# ZAtechSensor3_v1_01.net
KiCad netlist of a schematic drawn in Altium Designer
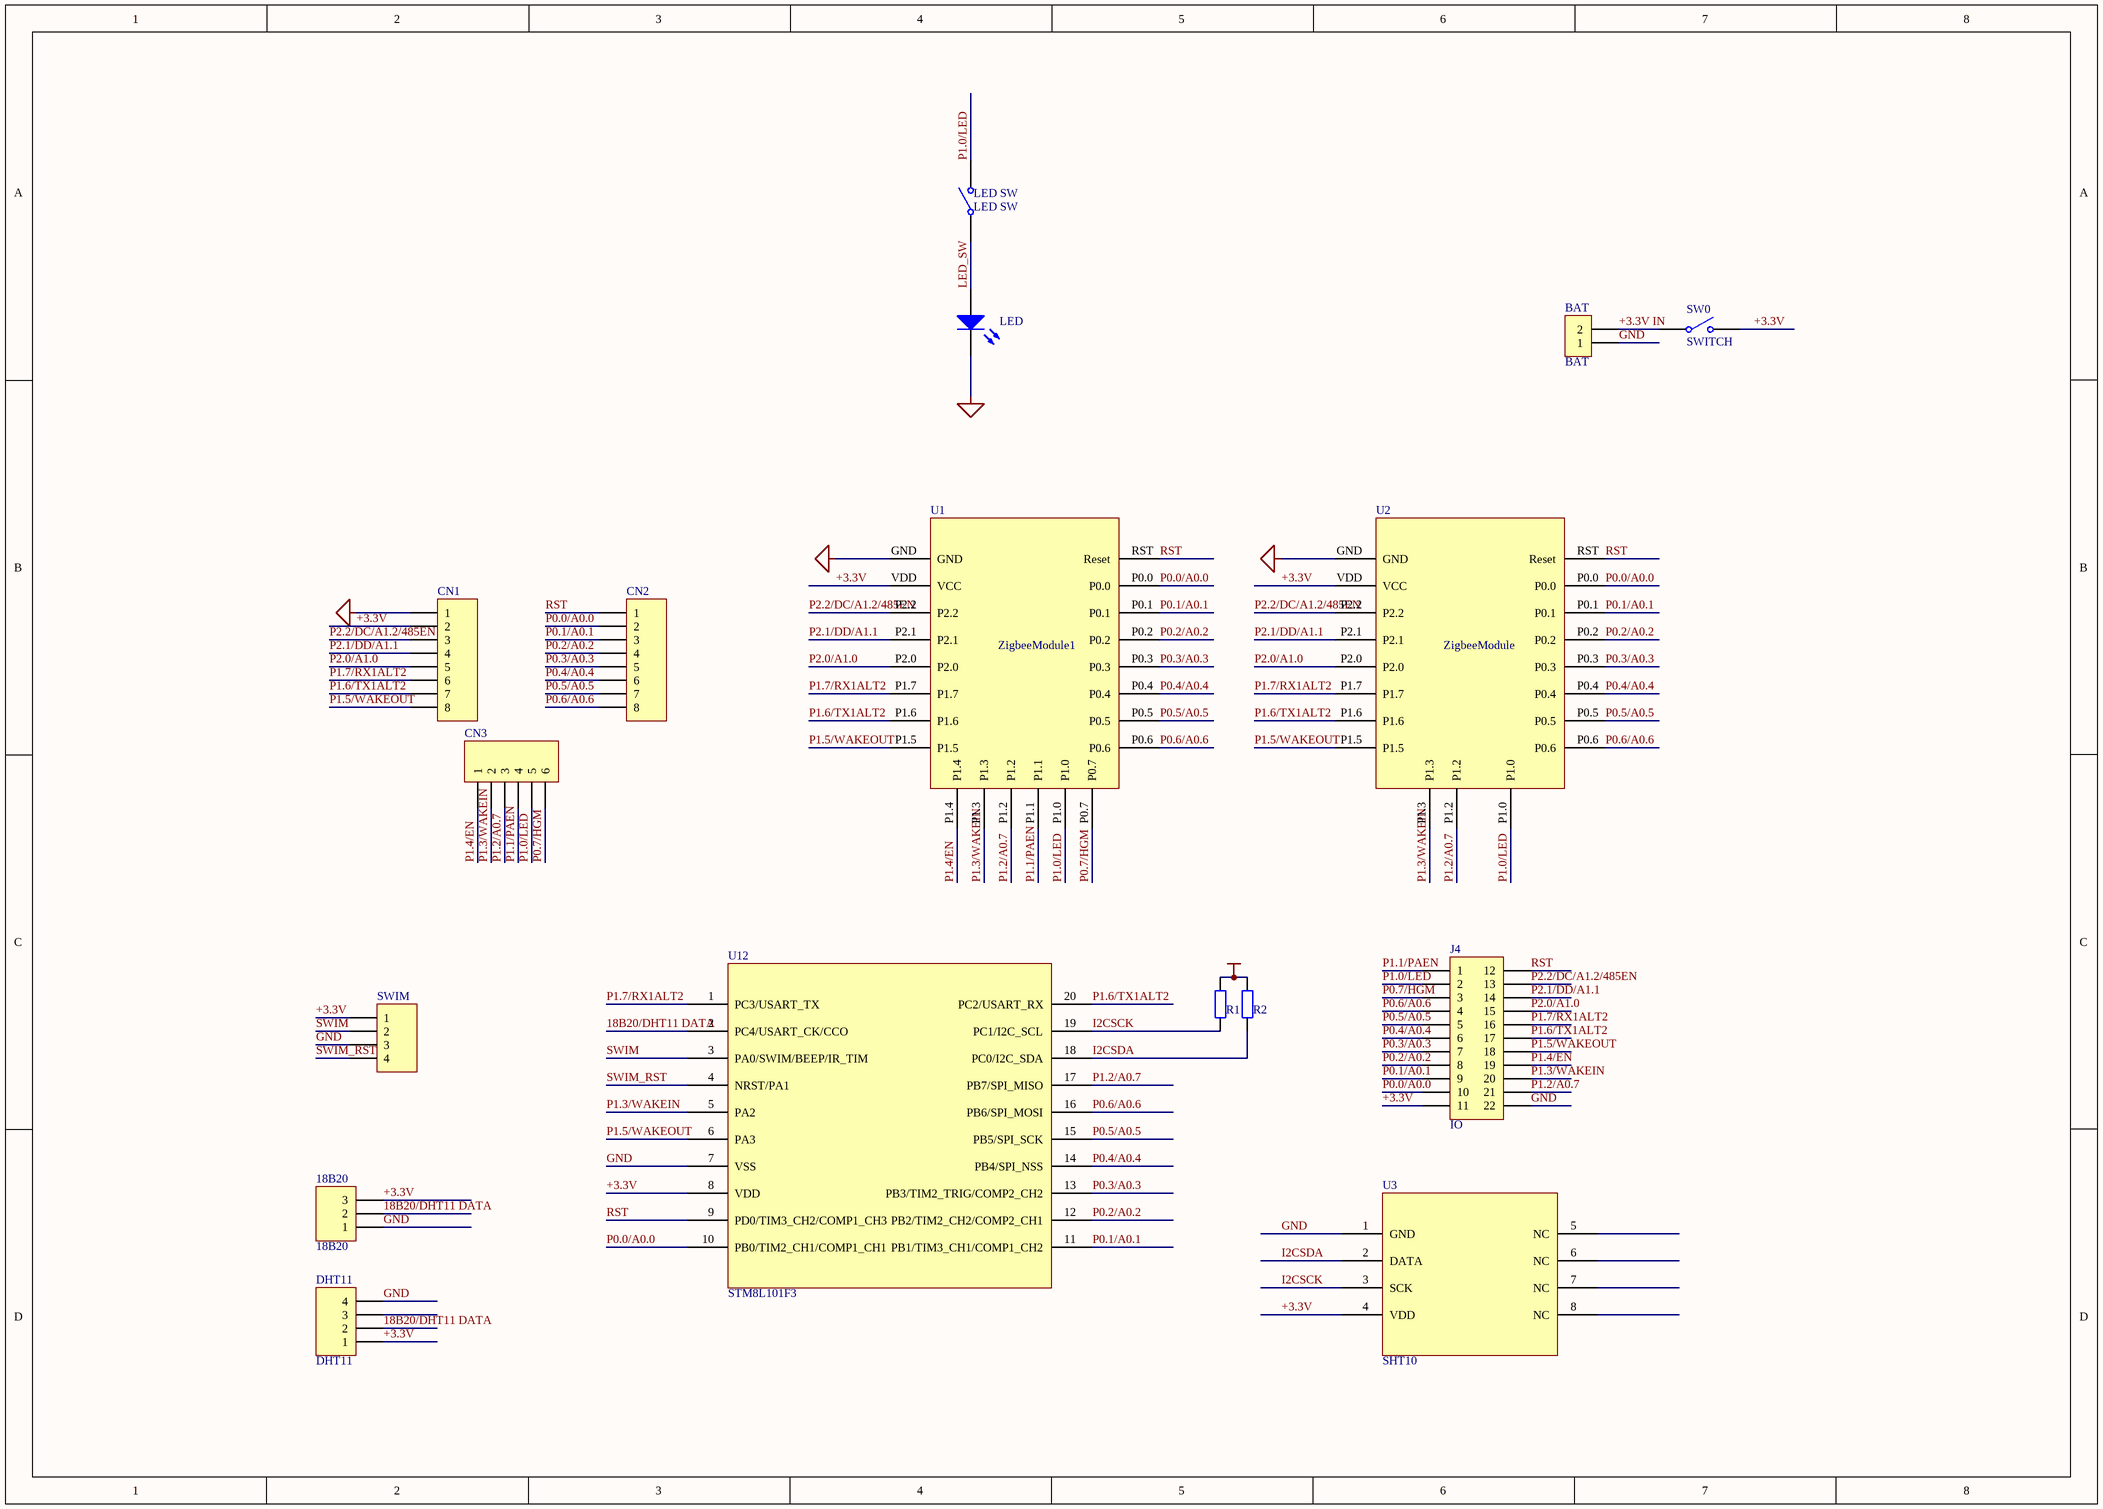
[diagram p0: ZAtechSensor3 v1_01.SCHDOC]

(export (version "E")
  (design (tool "Eeschema 10.0.6"))
  (components
    (comp (ref "18B20")
      (value "18B20")
      (footprint "BCY-W3")
      (description "Header, 3-Pin")
      (fields (field (name "PUBLISHER") "Altium Limited"))
      (libsource (lib "Miscellaneous Connectors") (part "Header 3"))
    )
    (comp (ref "BAT") (value "BAT") (footprint "HDR1X2") (libsource (lib "总lib库") (part "CON2")))
    (comp (ref "CN1")
      (value "~")
      (footprint "HDR1X8")
      (description "Header, 8-Pin")
      (fields (field (name "PUBLISHER") "Altium Limited"))
      (libsource (lib "Miscellaneous Connectors") (part "Header 8"))
    )
    (comp (ref "CN2")
      (value "~")
      (footprint "HDR1X8")
      (description "Header, 8-Pin")
      (fields (field (name "PUBLISHER") "Altium Limited"))
      (libsource (lib "Miscellaneous Connectors") (part "Header 8"))
    )
    (comp (ref "CN3")
      (value "~")
      (footprint "HDR1X6")
      (description "Header, 6-Pin")
      (fields (field (name "PUBLISHER") "Altium Limited"))
      (libsource (lib "Miscellaneous Connectors") (part "Header 6"))
    )
    (comp (ref "DHT11")
      (value "DHT11")
      (footprint "HDR1X4")
      (description "Header, 4-Pin")
      (fields (field (name "PUBLISHER") "Altium Limited"))
      (libsource (lib "") (part "Header 4_1"))
    )
    (comp (ref "J4")
      (value "IO")
      (footprint "HDR2X11_CEN")
      (description "Header, 11-Pin, Dual row")
      (fields (field (name "PUBLISHER") "Altium Limited"))
      (libsource (lib "Miscellaneous Connectors") (part "Header 11X2A"))
    )
    (comp (ref "LED")
      (value "LED3")
      (footprint "LED1-3MM")
      (description "Typical BLUE SiC LED")
      (fields (field (name "PUBLISHER") "Altium Limited"))
      (libsource (lib "Miscellaneous Devices") (part "LED3"))
    )
    (comp (ref "LED SW")
      (value "LED SW")
      (footprint "HDR1X2")
      (description "Single-Pole, Single-Throw Switch")
      (fields (field (name "PUBLISHER") "Altium Limited"))
      (libsource (lib "Miscellaneous Devices") (part "SW-SPST"))
    )
    (comp (ref "R1")
      (value "4.7K")
      (footprint "0402")
      (description "Resistor")
      (libsource (lib "Miscellaneous Devices") (part "Res2"))
    )
    (comp (ref "R2")
      (value "4.7K")
      (footprint "0402")
      (description "Resistor")
      (libsource (lib "Miscellaneous Devices") (part "Res2"))
    )
    (comp (ref "SW0")
      (value "SWITCH")
      (footprint "SW5")
      (description "Single-Pole, Single-Throw Switch")
      (fields (field (name "PUBLISHER") "Altium Limited"))
      (libsource (lib "") (part "SW-SPST_1"))
    )
    (comp (ref "SWIM")
      (value "RST  GND  DATA  VDD")
      (footprint "HDR1X4")
      (description "Header, 4-Pin")
      (fields (field (name "PUBLISHER") "Altium Limited"))
      (libsource (lib "Miscellaneous Connectors") (part "Header 4"))
    )
    (comp (ref "U1")
      (value "ZigbeeModule1")
      (footprint "2530Module1")
      (libsource (lib "ZigbeeModule") (part "Component_1"))
    )
    (comp (ref "U2")
      (value "ZigbeeModule")
      (footprint "2591Module")
      (libsource (lib "") (part "Component_1_1"))
    )
    (comp (ref "U3") (value "SHT10") (libsource (lib "SHT10") (part "SHT10")))
    (comp (ref "U12")
      (value "STM8L101F3")
      (footprint "TSSOP20")
      (libsource (lib "STM8L101F3") (part "STM8L101F3"))
    )
  )
  (nets
    (net (code "1") (name "+3.3V") (class "Default")
      (node (ref "18B20") (pin "3") (pinfunction "3_3") (pintype "passive"))
      (node (ref "CN1") (pin "2") (pinfunction "2_2") (pintype "passive"))
      (node (ref "DHT11") (pin "1") (pinfunction "1_1") (pintype "passive"))
      (node (ref "J4") (pin "11") (pinfunction "11_11") (pintype "passive"))
      (node (ref "R1") (pin "1") (pinfunction "1_1") (pintype "passive"))
      (node (ref "R2") (pin "1") (pinfunction "1_1") (pintype "passive"))
      (node (ref "SW0") (pin "2") (pinfunction "2_2") (pintype "passive"))
      (node (ref "SWIM") (pin "1") (pinfunction "1_1") (pintype "passive"))
      (node (ref "U1") (pin "VDD") (pinfunction "VCC_VDD") (pintype "passive"))
      (node (ref "U12") (pin "8") (pinfunction "VDD_8") (pintype "passive"))
      (node (ref "U2") (pin "VDD") (pinfunction "VCC_VDD") (pintype "passive"))
      (node (ref "U3") (pin "4") (pinfunction "VDD_4") (pintype "passive"))
    )
    (net (code "2") (name "/+3.3V IN") (class "Default")
      (node (ref "BAT") (pin "2") (pinfunction "2_2") (pintype "passive"))
      (node (ref "SW0") (pin "1") (pinfunction "1_1") (pintype "passive"))
    )
    (net (code "3") (name "/18B20{slash}DHT11 DATA") (class "Default")
      (node (ref "18B20") (pin "2") (pinfunction "2_2") (pintype "passive"))
      (node (ref "DHT11") (pin "2") (pinfunction "2_2") (pintype "passive"))
      (node (ref "U12") (pin "2") (pinfunction "PC4/USART_CK/CCO_2") (pintype "passive"))
    )
    (net (code "4") (name "/I2CSCK") (class "Default")
      (node (ref "R1") (pin "2") (pinfunction "2_2") (pintype "passive"))
      (node (ref "U12") (pin "19") (pinfunction "PC1/I2C_SCL_19") (pintype "passive"))
      (node (ref "U3") (pin "3") (pinfunction "SCK_3") (pintype "passive"))
    )
    (net (code "5") (name "/I2CSDA") (class "Default")
      (node (ref "R2") (pin "2") (pinfunction "2_2") (pintype "passive"))
      (node (ref "U12") (pin "18") (pinfunction "PC0/I2C_SDA_18") (pintype "passive"))
      (node (ref "U3") (pin "2") (pinfunction "DATA_2") (pintype "passive"))
    )
    (net (code "6") (name "/LED_SW") (class "Default")
      (node (ref "LED") (pin "1") (pinfunction "A_1") (pintype "passive"))
      (node (ref "LED SW") (pin "1") (pinfunction "COMMON_1") (pintype "passive"))
    )
    (net (code "7") (name "/P0.0{slash}A0.0") (class "Default")
      (node (ref "CN2") (pin "2") (pinfunction "2_2") (pintype "passive"))
      (node (ref "J4") (pin "10") (pinfunction "10_10") (pintype "passive"))
      (node (ref "U1") (pin "P0.0") (pinfunction "P0.0_P0.0") (pintype "passive"))
      (node (ref "U12") (pin "10") (pinfunction "PB0/TIM2_CH1/COMP1_CH1_10") (pintype "passive"))
      (node (ref "U2") (pin "P0.0") (pinfunction "P0.0_P0.0") (pintype "passive"))
    )
    (net (code "8") (name "/P0.1{slash}A0.1") (class "Default")
      (node (ref "CN2") (pin "3") (pinfunction "3_3") (pintype "passive"))
      (node (ref "J4") (pin "9") (pinfunction "9_9") (pintype "passive"))
      (node (ref "U1") (pin "P0.1") (pinfunction "P0.1_P0.1") (pintype "passive"))
      (node (ref "U12") (pin "11") (pinfunction "PB1/TIM3_CH1/COMP1_CH2_11") (pintype "passive"))
      (node (ref "U2") (pin "P0.1") (pinfunction "P0.1_P0.1") (pintype "passive"))
    )
    (net (code "9") (name "/P0.2{slash}A0.2") (class "Default")
      (node (ref "CN2") (pin "4") (pinfunction "4_4") (pintype "passive"))
      (node (ref "J4") (pin "8") (pinfunction "8_8") (pintype "passive"))
      (node (ref "U1") (pin "P0.2") (pinfunction "P0.2_P0.2") (pintype "passive"))
      (node (ref "U12") (pin "12") (pinfunction "PB2/TIM2_CH2/COMP2_CH1_12") (pintype "passive"))
      (node (ref "U2") (pin "P0.2") (pinfunction "P0.2_P0.2") (pintype "passive"))
    )
    (net (code "10") (name "/P0.3{slash}A0.3") (class "Default")
      (node (ref "CN2") (pin "5") (pinfunction "5_5") (pintype "passive"))
      (node (ref "J4") (pin "7") (pinfunction "7_7") (pintype "passive"))
      (node (ref "U1") (pin "P0.3") (pinfunction "P0.3_P0.3") (pintype "passive"))
      (node (ref "U12") (pin "13") (pinfunction "PB3/TIM2_TRIG/COMP2_CH2_13") (pintype "passive"))
      (node (ref "U2") (pin "P0.3") (pinfunction "P0.3_P0.3") (pintype "passive"))
    )
    (net (code "11") (name "/P0.4{slash}A0.4") (class "Default")
      (node (ref "CN2") (pin "6") (pinfunction "6_6") (pintype "passive"))
      (node (ref "J4") (pin "6") (pinfunction "6_6") (pintype "passive"))
      (node (ref "U1") (pin "P0.4") (pinfunction "P0.4_P0.4") (pintype "passive"))
      (node (ref "U12") (pin "14") (pinfunction "PB4/SPI_NSS_14") (pintype "passive"))
      (node (ref "U2") (pin "P0.4") (pinfunction "P0.4_P0.4") (pintype "passive"))
    )
    (net (code "12") (name "/P0.5{slash}A0.5") (class "Default")
      (node (ref "CN2") (pin "7") (pinfunction "7_7") (pintype "passive"))
      (node (ref "J4") (pin "5") (pinfunction "5_5") (pintype "passive"))
      (node (ref "U1") (pin "P0.5") (pinfunction "P0.5_P0.5") (pintype "passive"))
      (node (ref "U12") (pin "15") (pinfunction "PB5/SPI_SCK_15") (pintype "passive"))
      (node (ref "U2") (pin "P0.5") (pinfunction "P0.5_P0.5") (pintype "passive"))
    )
    (net (code "13") (name "/P0.6{slash}A0.6") (class "Default")
      (node (ref "CN2") (pin "8") (pinfunction "8_8") (pintype "passive"))
      (node (ref "J4") (pin "4") (pinfunction "4_4") (pintype "passive"))
      (node (ref "U1") (pin "P0.6") (pinfunction "P0.6_P0.6") (pintype "passive"))
      (node (ref "U12") (pin "16") (pinfunction "PB6/SPI_MOSI_16") (pintype "passive"))
      (node (ref "U2") (pin "P0.6") (pinfunction "P0.6_P0.6") (pintype "passive"))
    )
    (net (code "14") (name "/P0.7{slash}HGM") (class "Default")
      (node (ref "CN3") (pin "6") (pinfunction "6_6") (pintype "passive"))
      (node (ref "J4") (pin "3") (pinfunction "3_3") (pintype "passive"))
      (node (ref "U1") (pin "P0.7") (pinfunction "P0.7_P0.7") (pintype "passive"))
    )
    (net (code "15") (name "/P1.0{slash}LED") (class "Default")
      (node (ref "CN3") (pin "5") (pinfunction "5_5") (pintype "passive"))
      (node (ref "J4") (pin "2") (pinfunction "2_2") (pintype "passive"))
      (node (ref "LED SW") (pin "2") (pinfunction "NO_2") (pintype "passive"))
      (node (ref "U1") (pin "P1.0") (pinfunction "P1.0_P1.0") (pintype "passive"))
      (node (ref "U2") (pin "P1.0") (pinfunction "P1.0_P1.0") (pintype "passive"))
    )
    (net (code "16") (name "/P1.1{slash}PAEN") (class "Default")
      (node (ref "CN3") (pin "4") (pinfunction "4_4") (pintype "passive"))
      (node (ref "J4") (pin "1") (pinfunction "1_1") (pintype "passive"))
      (node (ref "U1") (pin "P1.1") (pinfunction "P1.1_P1.1") (pintype "passive"))
    )
    (net (code "17") (name "/P1.2{slash}A0.7") (class "Default")
      (node (ref "CN3") (pin "3") (pinfunction "3_3") (pintype "passive"))
      (node (ref "J4") (pin "21") (pinfunction "21_21") (pintype "passive"))
      (node (ref "U1") (pin "P1.2") (pinfunction "P1.2_P1.2") (pintype "passive"))
      (node (ref "U12") (pin "17") (pinfunction "PB7/SPI_MISO_17") (pintype "passive"))
      (node (ref "U2") (pin "P1.2") (pinfunction "P1.2_P1.2") (pintype "passive"))
    )
    (net (code "18") (name "/P1.3{slash}WAKEIN") (class "Default")
      (node (ref "CN3") (pin "2") (pinfunction "2_2") (pintype "passive"))
      (node (ref "J4") (pin "20") (pinfunction "20_20") (pintype "passive"))
      (node (ref "U1") (pin "P1.3") (pinfunction "P1.3_P1.3") (pintype "passive"))
      (node (ref "U12") (pin "5") (pinfunction "PA2_5") (pintype "passive"))
      (node (ref "U2") (pin "P1.3") (pinfunction "P1.3_P1.3") (pintype "passive"))
    )
    (net (code "19") (name "/P1.4{slash}EN") (class "Default")
      (node (ref "CN3") (pin "1") (pinfunction "1_1") (pintype "passive"))
      (node (ref "J4") (pin "19") (pinfunction "19_19") (pintype "passive"))
      (node (ref "U1") (pin "P1.4") (pinfunction "P1.4_P1.4") (pintype "passive"))
    )
    (net (code "20") (name "/P1.5{slash}WAKEOUT") (class "Default")
      (node (ref "CN1") (pin "8") (pinfunction "8_8") (pintype "passive"))
      (node (ref "J4") (pin "18") (pinfunction "18_18") (pintype "passive"))
      (node (ref "U1") (pin "P1.5") (pinfunction "P1.5_P1.5") (pintype "passive"))
      (node (ref "U12") (pin "6") (pinfunction "PA3_6") (pintype "passive"))
      (node (ref "U2") (pin "P1.5") (pinfunction "P1.5_P1.5") (pintype "passive"))
    )
    (net (code "21") (name "/P1.6{slash}TX1ALT2") (class "Default")
      (node (ref "CN1") (pin "7") (pinfunction "7_7") (pintype "passive"))
      (node (ref "J4") (pin "17") (pinfunction "17_17") (pintype "passive"))
      (node (ref "U1") (pin "P1.6") (pinfunction "P1.6_P1.6") (pintype "passive"))
      (node (ref "U12") (pin "20") (pinfunction "PC2/USART_RX_20") (pintype "passive"))
      (node (ref "U2") (pin "P1.6") (pinfunction "P1.6_P1.6") (pintype "passive"))
    )
    (net (code "22") (name "/P1.7{slash}RX1ALT2") (class "Default")
      (node (ref "CN1") (pin "6") (pinfunction "6_6") (pintype "passive"))
      (node (ref "J4") (pin "16") (pinfunction "16_16") (pintype "passive"))
      (node (ref "U1") (pin "P1.7") (pinfunction "P1.7_P1.7") (pintype "passive"))
      (node (ref "U12") (pin "1") (pinfunction "PC3/USART_TX_1") (pintype "passive"))
      (node (ref "U2") (pin "P1.7") (pinfunction "P1.7_P1.7") (pintype "passive"))
    )
    (net (code "23") (name "/P2.0{slash}A1.0") (class "Default")
      (node (ref "CN1") (pin "5") (pinfunction "5_5") (pintype "passive"))
      (node (ref "J4") (pin "15") (pinfunction "15_15") (pintype "passive"))
      (node (ref "U1") (pin "P2.0") (pinfunction "P2.0_P2.0") (pintype "passive"))
      (node (ref "U2") (pin "P2.0") (pinfunction "P2.0_P2.0") (pintype "passive"))
    )
    (net (code "24") (name "/P2.1{slash}DD{slash}A1.1") (class "Default")
      (node (ref "CN1") (pin "4") (pinfunction "4_4") (pintype "passive"))
      (node (ref "J4") (pin "14") (pinfunction "14_14") (pintype "passive"))
      (node (ref "U1") (pin "P2.1") (pinfunction "P2.1_P2.1") (pintype "passive"))
      (node (ref "U2") (pin "P2.1") (pinfunction "P2.1_P2.1") (pintype "passive"))
    )
    (net (code "25") (name "/P2.2{slash}DC{slash}A1.2{slash}485EN") (class "Default")
      (node (ref "CN1") (pin "3") (pinfunction "3_3") (pintype "passive"))
      (node (ref "J4") (pin "13") (pinfunction "13_13") (pintype "passive"))
      (node (ref "U1") (pin "P2.2") (pinfunction "P2.2_P2.2") (pintype "passive"))
      (node (ref "U2") (pin "P2.2") (pinfunction "P2.2_P2.2") (pintype "passive"))
    )
    (net (code "26") (name "/RST") (class "Default")
      (node (ref "CN2") (pin "1") (pinfunction "1_1") (pintype "passive"))
      (node (ref "J4") (pin "12") (pinfunction "12_12") (pintype "passive"))
      (node (ref "U1") (pin "RST") (pinfunction "Reset_RST") (pintype "passive"))
      (node (ref "U12") (pin "9") (pinfunction "PD0/TIM3_CH2/COMP1_CH3_9") (pintype "passive"))
      (node (ref "U2") (pin "RST") (pinfunction "Reset_RST") (pintype "passive"))
    )
    (net (code "27") (name "/SWIM") (class "Default")
      (node (ref "SWIM") (pin "2") (pinfunction "2_2") (pintype "passive"))
      (node (ref "U12") (pin "3") (pinfunction "PA0/SWIM/BEEP/IR_TIM_3") (pintype "passive"))
    )
    (net (code "28") (name "/SWIM_RST") (class "Default")
      (node (ref "SWIM") (pin "4") (pinfunction "4_4") (pintype "passive"))
      (node (ref "U12") (pin "4") (pinfunction "NRST/PA1_4") (pintype "passive"))
    )
    (net (code "29") (name "GND") (class "Default")
      (node (ref "18B20") (pin "1") (pinfunction "1_1") (pintype "passive"))
      (node (ref "BAT") (pin "1") (pinfunction "1_1") (pintype "passive"))
      (node (ref "CN1") (pin "1") (pinfunction "1_1") (pintype "passive"))
      (node (ref "DHT11") (pin "4") (pinfunction "4_4") (pintype "passive"))
      (node (ref "J4") (pin "22") (pinfunction "22_22") (pintype "passive"))
      (node (ref "LED") (pin "2") (pinfunction "K_2") (pintype "passive"))
      (node (ref "SWIM") (pin "3") (pinfunction "3_3") (pintype "passive"))
      (node (ref "U1") (pin "GND") (pinfunction "GND_GND") (pintype "passive"))
      (node (ref "U12") (pin "7") (pinfunction "VSS_7") (pintype "passive"))
      (node (ref "U2") (pin "GND") (pinfunction "GND_GND") (pintype "passive"))
      (node (ref "U3") (pin "1") (pinfunction "GND_1") (pintype "passive"))
    )
    (net (code "30") (name "unconnected-(DHT11-Pad3)") (class "Default")
      (node (ref "DHT11") (pin "3") (pinfunction "3_3") (pintype "passive"))
    )
    (net (code "31") (name "unconnected-(U3-NC-Pad5)") (class "Default")
      (node (ref "U3") (pin "5") (pinfunction "NC_5") (pintype "passive"))
    )
    (net (code "32") (name "unconnected-(U3-NC-Pad6)") (class "Default")
      (node (ref "U3") (pin "6") (pinfunction "NC_6") (pintype "passive"))
    )
    (net (code "33") (name "unconnected-(U3-NC-Pad7)") (class "Default")
      (node (ref "U3") (pin "7") (pinfunction "NC_7") (pintype "passive"))
    )
    (net (code "34") (name "unconnected-(U3-NC-Pad8)") (class "Default")
      (node (ref "U3") (pin "8") (pinfunction "NC_8") (pintype "passive"))
    )
  )
)
